# basic_schematic_input.net
KiCad netlist of a schematic drawn in EAGLE
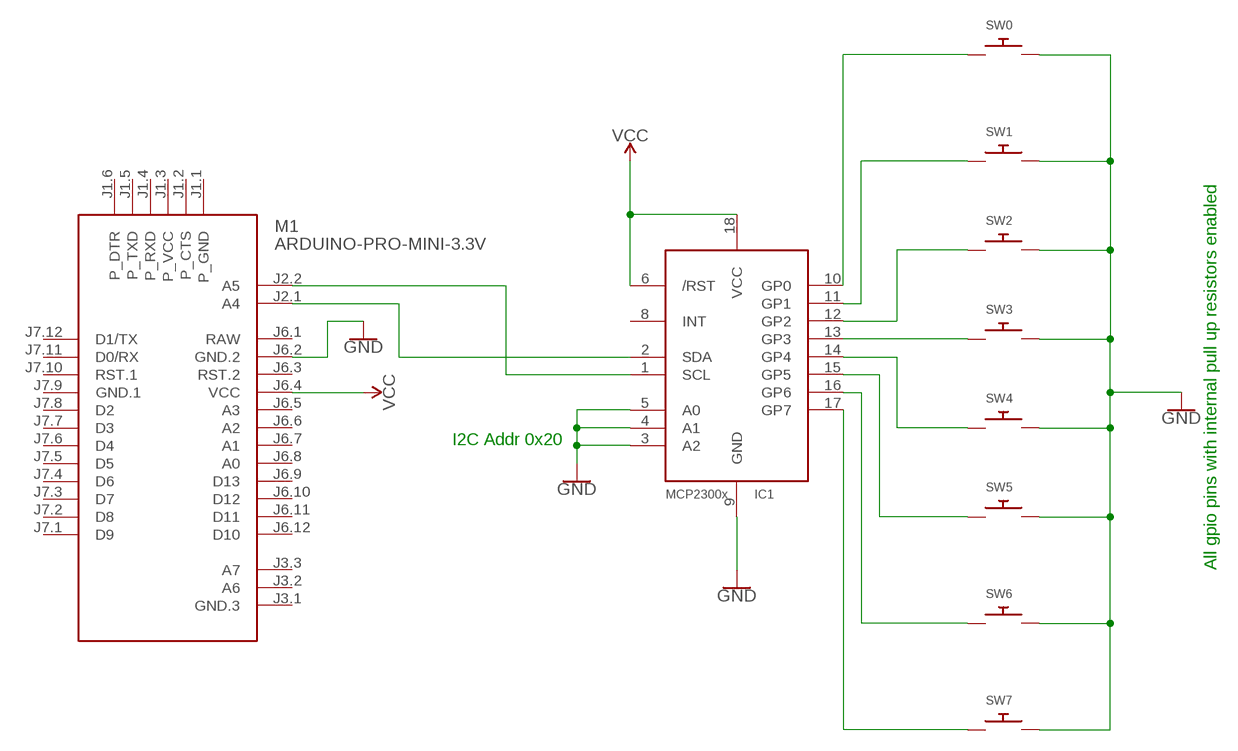
[diagram p0: schematic, sheet 1]

(export (version "E")
  (design (tool "Eeschema 10.0.6"))
  (components
    (comp (ref "IC1")
      (value "MCP23008/SO")
      (footprint "eagle-import:SO18W")
      (libsource (lib "eagle-import") (part "MCP23008/SO"))
    )
    (comp (ref "M1")
      (value "ARDUINO-PRO-MINI-3.3V")
      (footprint "eagle-import:ARDUINO-PRO-MINI")
      (libsource (lib "eagle-import") (part "ARDUINO-PRO-MINI-3.3V"))
    )
    (comp (ref "SW0")
      (value "SWITCH_PUSHBUTTONC&K_KSS")
      (footprint "eagle-import:BTN_CK_KSS")
      (libsource (lib "eagle-import") (part "SWITCH_PUSHBUTTONC&K_KSS"))
    )
    (comp (ref "SW1")
      (value "SWITCH_PUSHBUTTONC&K_KSS")
      (footprint "eagle-import:BTN_CK_KSS")
      (libsource (lib "eagle-import") (part "SWITCH_PUSHBUTTONC&K_KSS"))
    )
    (comp (ref "SW2")
      (value "SWITCH_PUSHBUTTONC&K_KSS")
      (footprint "eagle-import:BTN_CK_KSS")
      (libsource (lib "eagle-import") (part "SWITCH_PUSHBUTTONC&K_KSS"))
    )
    (comp (ref "SW3")
      (value "SWITCH_PUSHBUTTONC&K_KSS")
      (footprint "eagle-import:BTN_CK_KSS")
      (libsource (lib "eagle-import") (part "SWITCH_PUSHBUTTONC&K_KSS"))
    )
    (comp (ref "SW4")
      (value "SWITCH_PUSHBUTTONC&K_KSS")
      (footprint "eagle-import:BTN_CK_KSS")
      (libsource (lib "eagle-import") (part "SWITCH_PUSHBUTTONC&K_KSS"))
    )
    (comp (ref "SW5")
      (value "SWITCH_PUSHBUTTONC&K_KSS")
      (footprint "eagle-import:BTN_CK_KSS")
      (libsource (lib "eagle-import") (part "SWITCH_PUSHBUTTONC&K_KSS"))
    )
    (comp (ref "SW6")
      (value "SWITCH_PUSHBUTTONC&K_KSS")
      (footprint "eagle-import:BTN_CK_KSS")
      (libsource (lib "eagle-import") (part "SWITCH_PUSHBUTTONC&K_KSS"))
    )
    (comp (ref "SW7")
      (value "SWITCH_PUSHBUTTONC&K_KSS")
      (footprint "eagle-import:BTN_CK_KSS")
      (libsource (lib "eagle-import") (part "SWITCH_PUSHBUTTONC&K_KSS"))
    )
  )
  (nets
    (net (code "1") (name "/GND.1") (class "Default")
      (node (ref "M1") (pin "J7.9") (pinfunction "GND.1_J7.9") (pintype "power_in"))
    )
    (net (code "2") (name "/RAW") (class "Default")
      (node (ref "M1") (pin "J6.1") (pinfunction "RAW_J6.1") (pintype "power_in"))
    )
    (net (code "3") (name "GND") (class "Default")
      (node (ref "IC1") (pin "3") (pinfunction "A2_3") (pintype "input"))
      (node (ref "IC1") (pin "4") (pinfunction "A1_4") (pintype "input"))
      (node (ref "IC1") (pin "5") (pinfunction "A0_5") (pintype "input"))
      (node (ref "IC1") (pin "9") (pinfunction "GND_9") (pintype "power_in"))
      (node (ref "M1") (pin "J6.2") (pinfunction "GND.2_J6.2") (pintype "power_in"))
      (node (ref "SW0") (pin "P$2") (pinfunction "P$2_P$2") (pintype "passive"))
      (node (ref "SW1") (pin "P$2") (pinfunction "P$2_P$2") (pintype "passive"))
      (node (ref "SW2") (pin "P$2") (pinfunction "P$2_P$2") (pintype "passive"))
      (node (ref "SW3") (pin "P$2") (pinfunction "P$2_P$2") (pintype "passive"))
      (node (ref "SW4") (pin "P$2") (pinfunction "P$2_P$2") (pintype "passive"))
      (node (ref "SW5") (pin "P$2") (pinfunction "P$2_P$2") (pintype "passive"))
      (node (ref "SW6") (pin "P$2") (pinfunction "P$2_P$2") (pintype "passive"))
      (node (ref "SW7") (pin "P$2") (pinfunction "P$2_P$2") (pintype "passive"))
    )
    (net (code "4") (name "Net-(IC1-GP0)") (class "Default")
      (node (ref "IC1") (pin "10") (pinfunction "GP0_10") (pintype "bidirectional"))
      (node (ref "SW0") (pin "P$1") (pinfunction "P$1_P$1") (pintype "passive"))
    )
    (net (code "5") (name "Net-(IC1-GP1)") (class "Default")
      (node (ref "IC1") (pin "11") (pinfunction "GP1_11") (pintype "bidirectional"))
      (node (ref "SW1") (pin "P$1") (pinfunction "P$1_P$1") (pintype "passive"))
    )
    (net (code "6") (name "Net-(IC1-GP2)") (class "Default")
      (node (ref "IC1") (pin "12") (pinfunction "GP2_12") (pintype "bidirectional"))
      (node (ref "SW2") (pin "P$1") (pinfunction "P$1_P$1") (pintype "passive"))
    )
    (net (code "7") (name "Net-(IC1-GP3)") (class "Default")
      (node (ref "IC1") (pin "13") (pinfunction "GP3_13") (pintype "bidirectional"))
      (node (ref "SW3") (pin "P$1") (pinfunction "P$1_P$1") (pintype "passive"))
    )
    (net (code "8") (name "Net-(IC1-GP4)") (class "Default")
      (node (ref "IC1") (pin "14") (pinfunction "GP4_14") (pintype "bidirectional"))
      (node (ref "SW4") (pin "P$1") (pinfunction "P$1_P$1") (pintype "passive"))
    )
    (net (code "9") (name "Net-(IC1-GP5)") (class "Default")
      (node (ref "IC1") (pin "15") (pinfunction "GP5_15") (pintype "bidirectional"))
      (node (ref "SW5") (pin "P$1") (pinfunction "P$1_P$1") (pintype "passive"))
    )
    (net (code "10") (name "Net-(IC1-GP6)") (class "Default")
      (node (ref "IC1") (pin "16") (pinfunction "GP6_16") (pintype "bidirectional"))
      (node (ref "SW6") (pin "P$1") (pinfunction "P$1_P$1") (pintype "passive"))
    )
    (net (code "11") (name "Net-(IC1-GP7)") (class "Default")
      (node (ref "IC1") (pin "17") (pinfunction "GP7_17") (pintype "bidirectional"))
      (node (ref "SW7") (pin "P$1") (pinfunction "P$1_P$1") (pintype "passive"))
    )
    (net (code "12") (name "Net-(IC1-SCL)") (class "Default")
      (node (ref "IC1") (pin "1") (pinfunction "SCL_1") (pintype "bidirectional"))
      (node (ref "M1") (pin "J2.2") (pinfunction "A5_J2.2") (pintype "bidirectional"))
    )
    (net (code "13") (name "Net-(IC1-SDA)") (class "Default")
      (node (ref "IC1") (pin "2") (pinfunction "SDA_2") (pintype "bidirectional"))
      (node (ref "M1") (pin "J2.1") (pinfunction "A4_J2.1") (pintype "bidirectional"))
    )
    (net (code "14") (name "VCC") (class "Default")
      (node (ref "IC1") (pin "18") (pinfunction "VCC_18") (pintype "power_in"))
      (node (ref "IC1") (pin "6") (pinfunction "/RST_6") (pintype "input"))
      (node (ref "M1") (pin "J6.4") (pinfunction "VCC_J6.4") (pintype "power_in"))
    )
    (net (code "15") (name "unconnected-(IC1-INT-Pad8)") (class "Default")
      (node (ref "IC1") (pin "8") (pinfunction "INT_8") (pintype "output"))
    )
    (net (code "16") (name "unconnected-(M1-A0-PadJ6.8)") (class "Default")
      (node (ref "M1") (pin "J6.8") (pinfunction "A0_J6.8") (pintype "bidirectional"))
    )
    (net (code "17") (name "unconnected-(M1-A1-PadJ6.7)") (class "Default")
      (node (ref "M1") (pin "J6.7") (pinfunction "A1_J6.7") (pintype "bidirectional"))
    )
    (net (code "18") (name "unconnected-(M1-A2-PadJ6.6)") (class "Default")
      (node (ref "M1") (pin "J6.6") (pinfunction "A2_J6.6") (pintype "bidirectional"))
    )
    (net (code "19") (name "unconnected-(M1-A3-PadJ6.5)") (class "Default")
      (node (ref "M1") (pin "J6.5") (pinfunction "A3_J6.5") (pintype "bidirectional"))
    )
    (net (code "20") (name "unconnected-(M1-A6-PadJ3.2)") (class "Default")
      (node (ref "M1") (pin "J3.2") (pinfunction "A6_J3.2") (pintype "bidirectional"))
    )
    (net (code "21") (name "unconnected-(M1-A7-PadJ3.3)") (class "Default")
      (node (ref "M1") (pin "J3.3") (pinfunction "A7_J3.3") (pintype "bidirectional"))
    )
    (net (code "22") (name "unconnected-(M1-D0{slash}RX-PadJ7.11)") (class "Default")
      (node (ref "M1") (pin "J7.11") (pinfunction "D0/RX_J7.11") (pintype "bidirectional"))
    )
    (net (code "23") (name "unconnected-(M1-D1{slash}TX-PadJ7.12)") (class "Default")
      (node (ref "M1") (pin "J7.12") (pinfunction "D1/TX_J7.12") (pintype "bidirectional"))
    )
    (net (code "24") (name "unconnected-(M1-D2-PadJ7.8)") (class "Default")
      (node (ref "M1") (pin "J7.8") (pinfunction "D2_J7.8") (pintype "bidirectional"))
    )
    (net (code "25") (name "unconnected-(M1-D3-PadJ7.7)") (class "Default")
      (node (ref "M1") (pin "J7.7") (pinfunction "D3_J7.7") (pintype "bidirectional"))
    )
    (net (code "26") (name "unconnected-(M1-D4-PadJ7.6)") (class "Default")
      (node (ref "M1") (pin "J7.6") (pinfunction "D4_J7.6") (pintype "bidirectional"))
    )
    (net (code "27") (name "unconnected-(M1-D5-PadJ7.5)") (class "Default")
      (node (ref "M1") (pin "J7.5") (pinfunction "D5_J7.5") (pintype "bidirectional"))
    )
    (net (code "28") (name "unconnected-(M1-D6-PadJ7.4)") (class "Default")
      (node (ref "M1") (pin "J7.4") (pinfunction "D6_J7.4") (pintype "bidirectional"))
    )
    (net (code "29") (name "unconnected-(M1-D7-PadJ7.3)") (class "Default")
      (node (ref "M1") (pin "J7.3") (pinfunction "D7_J7.3") (pintype "bidirectional"))
    )
    (net (code "30") (name "unconnected-(M1-D8-PadJ7.2)") (class "Default")
      (node (ref "M1") (pin "J7.2") (pinfunction "D8_J7.2") (pintype "bidirectional"))
    )
    (net (code "31") (name "unconnected-(M1-D9-PadJ7.1)") (class "Default")
      (node (ref "M1") (pin "J7.1") (pinfunction "D9_J7.1") (pintype "bidirectional"))
    )
    (net (code "32") (name "unconnected-(M1-D10-PadJ6.12)") (class "Default")
      (node (ref "M1") (pin "J6.12") (pinfunction "D10_J6.12") (pintype "bidirectional"))
    )
    (net (code "33") (name "unconnected-(M1-D11-PadJ6.11)") (class "Default")
      (node (ref "M1") (pin "J6.11") (pinfunction "D11_J6.11") (pintype "bidirectional"))
    )
    (net (code "34") (name "unconnected-(M1-D12-PadJ6.10)") (class "Default")
      (node (ref "M1") (pin "J6.10") (pinfunction "D12_J6.10") (pintype "bidirectional"))
    )
    (net (code "35") (name "unconnected-(M1-D13-PadJ6.9)") (class "Default")
      (node (ref "M1") (pin "J6.9") (pinfunction "D13_J6.9") (pintype "bidirectional"))
    )
    (net (code "36") (name "unconnected-(M1-GND.3-PadJ3.1)") (class "Default")
      (node (ref "M1") (pin "J3.1") (pinfunction "GND.3_J3.1") (pintype "bidirectional"))
    )
    (net (code "37") (name "unconnected-(M1-P_CTS-PadJ1.2)") (class "Default")
      (node (ref "M1") (pin "J1.2") (pinfunction "P_CTS_J1.2") (pintype "bidirectional"))
    )
    (net (code "38") (name "unconnected-(M1-P_DTR-PadJ1.6)") (class "Default")
      (node (ref "M1") (pin "J1.6") (pinfunction "P_DTR_J1.6") (pintype "bidirectional"))
    )
    (net (code "39") (name "unconnected-(M1-P_GND-PadJ1.1)") (class "Default")
      (node (ref "M1") (pin "J1.1") (pinfunction "P_GND_J1.1") (pintype "bidirectional"))
    )
    (net (code "40") (name "unconnected-(M1-P_RXD-PadJ1.4)") (class "Default")
      (node (ref "M1") (pin "J1.4") (pinfunction "P_RXD_J1.4") (pintype "bidirectional"))
    )
    (net (code "41") (name "unconnected-(M1-P_TXD-PadJ1.5)") (class "Default")
      (node (ref "M1") (pin "J1.5") (pinfunction "P_TXD_J1.5") (pintype "bidirectional"))
    )
    (net (code "42") (name "unconnected-(M1-P_VCC-PadJ1.3)") (class "Default")
      (node (ref "M1") (pin "J1.3") (pinfunction "P_VCC_J1.3") (pintype "bidirectional"))
    )
    (net (code "43") (name "unconnected-(M1-RST.1-PadJ7.10)") (class "Default")
      (node (ref "M1") (pin "J7.10") (pinfunction "RST.1_J7.10") (pintype "bidirectional"))
    )
    (net (code "44") (name "unconnected-(M1-RST.2-PadJ6.3)") (class "Default")
      (node (ref "M1") (pin "J6.3") (pinfunction "RST.2_J6.3") (pintype "bidirectional"))
    )
  )
)
